# ACSN_v2.net
KiCad netlist of a schematic drawn in EAGLE
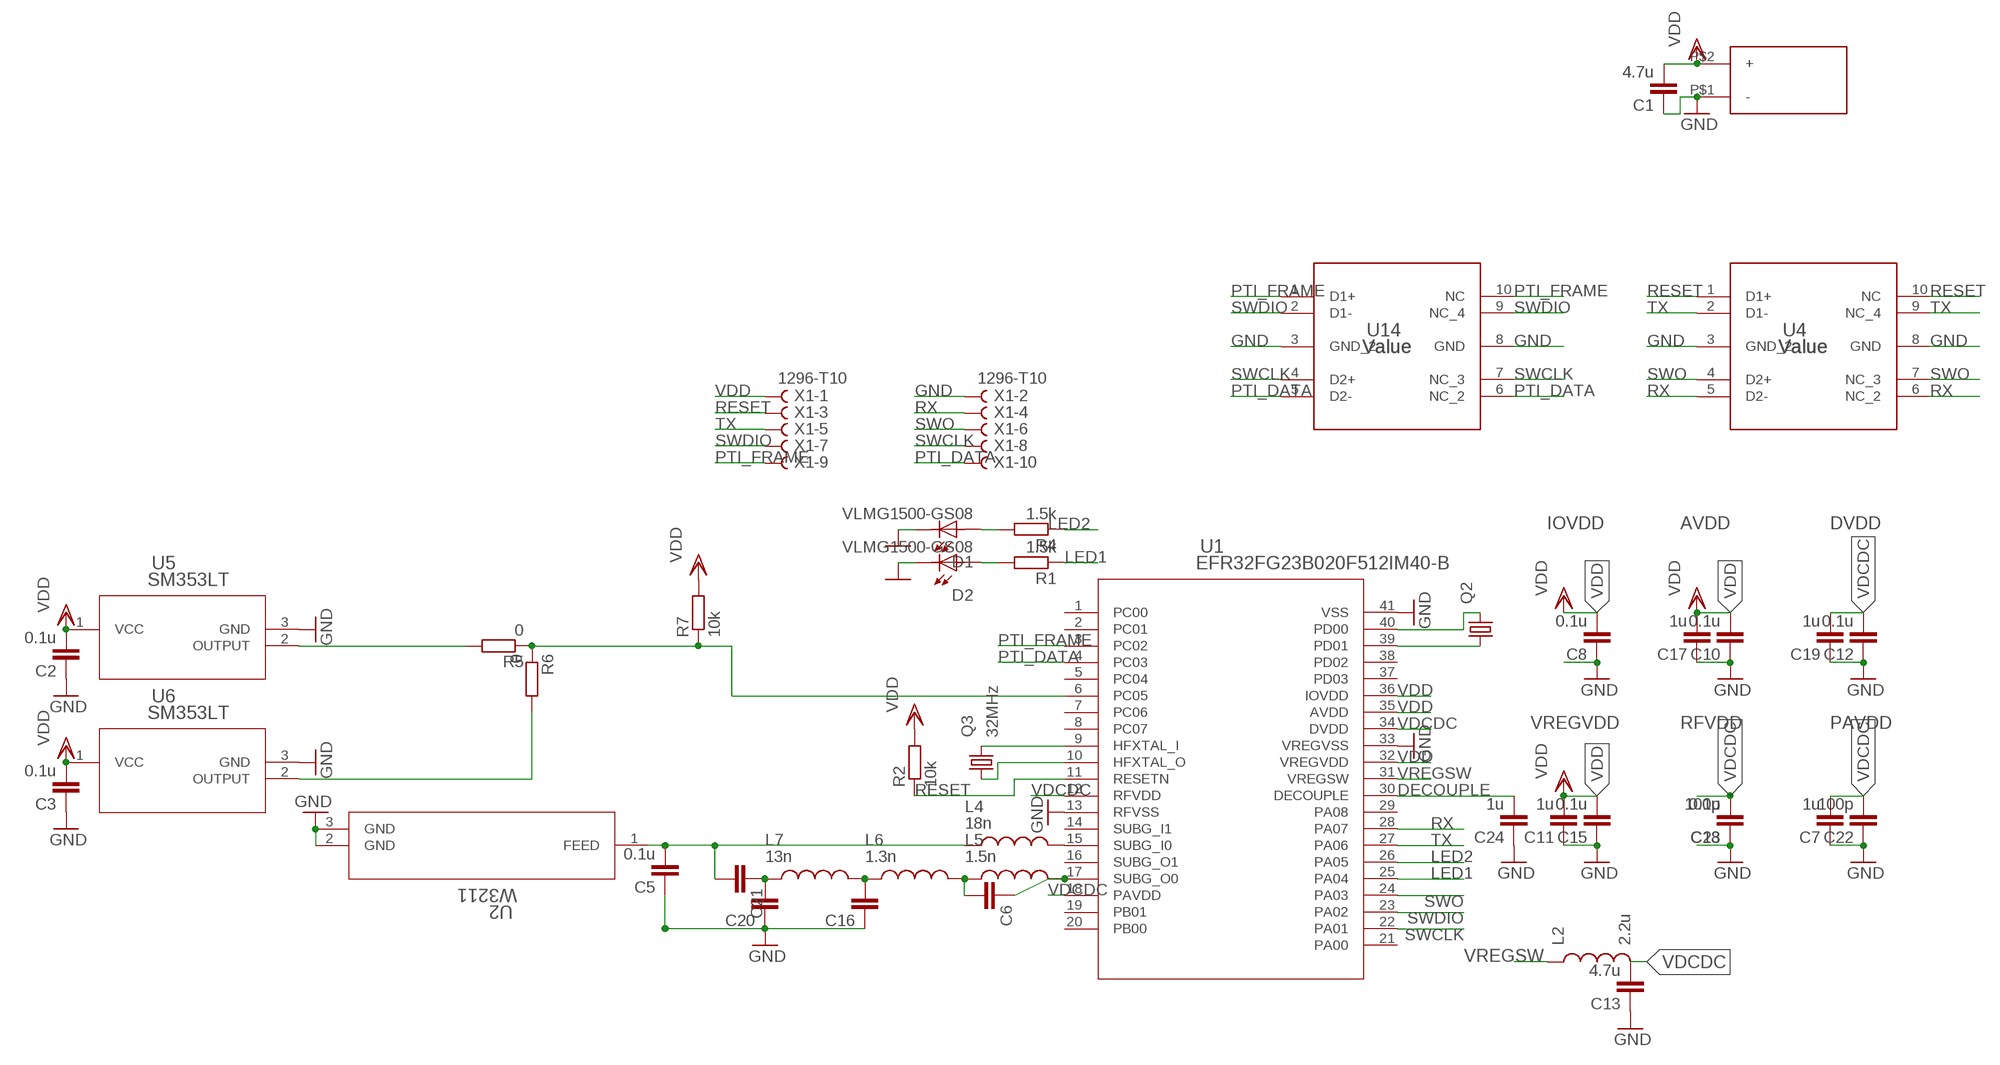
[diagram p0: schematic, sheet 1]

(export (version "E")
  (design (tool "Eeschema 10.0.6"))
  (components
    (comp (ref "C1")
      (value "4.7u")
      (footprint "eagle-import:C0603R")
      (libsource (lib "eagle-import") (part "CC0603R"))
    )
    (comp (ref "C2")
      (value "0.1u")
      (footprint "eagle-import:C0402")
      (libsource (lib "eagle-import") (part "CC0402"))
    )
    (comp (ref "C3")
      (value "0.1u")
      (footprint "eagle-import:C0402")
      (libsource (lib "eagle-import") (part "CC0402"))
    )
    (comp (ref "C5")
      (value "0.1u")
      (footprint "eagle-import:C0402")
      (libsource (lib "eagle-import") (part "CC0402"))
    )
    (comp (ref "C6")
      (value "1.9p")
      (footprint "eagle-import:C0402")
      (libsource (lib "eagle-import") (part "CC0402"))
    )
    (comp (ref "C7")
      (value "1u")
      (footprint "eagle-import:C0402")
      (libsource (lib "eagle-import") (part "CC0402"))
    )
    (comp (ref "C8")
      (value "0.1u")
      (footprint "eagle-import:C0402")
      (libsource (lib "eagle-import") (part "CC0402"))
    )
    (comp (ref "C10")
      (value "0.1u")
      (footprint "eagle-import:C0402")
      (libsource (lib "eagle-import") (part "CC0402"))
    )
    (comp (ref "C11")
      (value "1u")
      (footprint "eagle-import:C0402")
      (libsource (lib "eagle-import") (part "CC0402"))
    )
    (comp (ref "C12")
      (value "0.1u")
      (footprint "eagle-import:C0402")
      (libsource (lib "eagle-import") (part "CC0402"))
    )
    (comp (ref "C13")
      (value "4.7u")
      (footprint "eagle-import:C0603R")
      (libsource (lib "eagle-import") (part "CC0603R"))
    )
    (comp (ref "C15")
      (value "0.1u")
      (footprint "eagle-import:C0402")
      (libsource (lib "eagle-import") (part "CC0402"))
    )
    (comp (ref "C16")
      (value "7.2p")
      (footprint "eagle-import:C0402")
      (libsource (lib "eagle-import") (part "CC0402"))
    )
    (comp (ref "C17")
      (value "1u")
      (footprint "eagle-import:C0402")
      (libsource (lib "eagle-import") (part "CC0402"))
    )
    (comp (ref "C18")
      (value "0.1u")
      (footprint "eagle-import:C0402")
      (libsource (lib "eagle-import") (part "CC0402"))
    )
    (comp (ref "C19")
      (value "1u")
      (footprint "eagle-import:C0402")
      (libsource (lib "eagle-import") (part "CC0402"))
    )
    (comp (ref "C20")
      (value "1.3p")
      (footprint "eagle-import:C0402")
      (libsource (lib "eagle-import") (part "CC0402"))
    )
    (comp (ref "C21")
      (value "220p")
      (footprint "eagle-import:C0402")
      (libsource (lib "eagle-import") (part "CC0402"))
    )
    (comp (ref "C22")
      (value "100p")
      (footprint "eagle-import:C0402")
      (libsource (lib "eagle-import") (part "CC0402"))
    )
    (comp (ref "C23")
      (value "100p")
      (footprint "eagle-import:C0402")
      (libsource (lib "eagle-import") (part "CC0402"))
    )
    (comp (ref "C24")
      (value "1u")
      (footprint "eagle-import:C0402")
      (libsource (lib "eagle-import") (part "CC0402"))
    )
    (comp (ref "D1")
      (value "VLMG1500-GS08")
      (footprint "eagle-import:LEDC1005X35N")
      (fields (field (name "MF") "Vishay"))
      (libsource (lib "eagle-import") (part "VLMG1500-GS08"))
    )
    (comp (ref "D2")
      (value "VLMG1500-GS08")
      (footprint "eagle-import:LEDC1005X35N")
      (fields (field (name "MF") "Vishay"))
      (libsource (lib "eagle-import") (part "VLMG1500-GS08"))
    )
    (comp (ref "L2")
      (value "2.2u")
      (footprint "eagle-import:L0603")
      (libsource (lib "eagle-import") (part "INDUCTOR"))
    )
    (comp (ref "L4")
      (value "18n")
      (footprint "eagle-import:INDC0402X26N")
      (fields (field (name "MF") "TDK") (field (name "MP") "MHQ0402P7N5JT000"))
      (libsource (lib "eagle-import") (part "MHQ0402P7N5JT000"))
    )
    (comp (ref "L5")
      (value "1.5n")
      (footprint "eagle-import:INDC0402X26N")
      (fields (field (name "MF") "TDK") (field (name "MP") "MHQ0402P7N5JT000"))
      (libsource (lib "eagle-import") (part "MHQ0402P7N5JT000"))
    )
    (comp (ref "L6")
      (value "1.3n")
      (footprint "eagle-import:INDC0402X26N")
      (fields (field (name "MF") "TDK") (field (name "MP") "MHQ0402P7N5JT000"))
      (libsource (lib "eagle-import") (part "MHQ0402P7N5JT000"))
    )
    (comp (ref "L7")
      (value "13n")
      (footprint "eagle-import:INDC0402X26N")
      (fields (field (name "MF") "TDK") (field (name "MP") "MHQ0402P7N5JT000"))
      (libsource (lib "eagle-import") (part "MHQ0402P7N5JT000"))
    )
    (comp (ref "Q2")
      (value "KX-327-RT")
      (footprint "eagle-import:2.0X1.2")
      (libsource (lib "eagle-import") (part "KX-327-RT"))
    )
    (comp (ref "Q3")
      (value "32MHz")
      (footprint "eagle-import:2.0X1.6_KX-5")
      (libsource (lib "eagle-import") (part "KX-5"))
    )
    (comp (ref "R1")
      (value "1.5k")
      (footprint "eagle-import:R0402")
      (libsource (lib "eagle-import") (part "RR0402"))
    )
    (comp (ref "R2")
      (value "10k")
      (footprint "eagle-import:R0402")
      (libsource (lib "eagle-import") (part "RR0402"))
    )
    (comp (ref "R4")
      (value "1.5k")
      (footprint "eagle-import:R0402")
      (libsource (lib "eagle-import") (part "RR0402"))
    )
    (comp (ref "R5")
      (value "0")
      (footprint "eagle-import:R0402")
      (libsource (lib "eagle-import") (part "RR0402"))
    )
    (comp (ref "R6")
      (value "0")
      (footprint "eagle-import:R0402")
      (libsource (lib "eagle-import") (part "RR0402"))
    )
    (comp (ref "R7")
      (value "10k")
      (footprint "eagle-import:R0402")
      (libsource (lib "eagle-import") (part "RR0402"))
    )
    (comp (ref "U$2")
      (value "BS-24R")
      (footprint "eagle-import:BS-24")
      (libsource (lib "eagle-import") (part "BS-24R"))
    )
    (comp (ref "U1")
      (value "EFR32FG23B020F512IM40-B")
      (footprint "eagle-import:QFN_40_SIL")
      (fields (field (name "COPYRIGHT") "Copyright (C) 2022 Ultra Librarian. All rights reserved."))
      (libsource (lib "eagle-import") (part "EFR32FG23B020F512IM40-B"))
    )
    (comp (ref "U2")
      (value "W3211")
      (footprint "eagle-import:CHIP_3211_PUL")
      (fields (field (name "COPYRIGHT") "Copyright (C) 2022 Ultra Librarian. All rights reserved."))
      (libsource (lib "eagle-import") (part "W3211"))
    )
    (comp (ref "U4")
      (value "Value")
      (footprint "eagle-import:DQA0010A")
      (fields (field (name "MANUFACTURER") "Texas Instruments") (field (name "PARTNUMBER") "ESD204DQAR"))
      (libsource (lib "eagle-import") (part "ESD204DQAR"))
    )
    (comp (ref "U5")
      (value "SM353LT")
      (footprint "eagle-import:SM353LT_HNW")
      (fields (field (name "COPYRIGHT") "Copyright (C) 2022 Ultra Librarian. All rights reserved."))
      (libsource (lib "eagle-import") (part "SM353LT"))
    )
    (comp (ref "U6")
      (value "SM353LT")
      (footprint "eagle-import:SM353LT_HNW")
      (fields (field (name "COPYRIGHT") "Copyright (C) 2022 Ultra Librarian. All rights reserved."))
      (libsource (lib "eagle-import") (part "SM353LT"))
    )
    (comp (ref "U14")
      (value "Value")
      (footprint "eagle-import:DQA0010A")
      (fields (field (name "MANUFACTURER") "Texas Instruments") (field (name "PARTNUMBER") "ESD204DQAR"))
      (libsource (lib "eagle-import") (part "ESD204DQAR"))
    )
    (comp (ref "X1")
      (value "1296-T10")
      (footprint "eagle-import:1296-10")
      (libsource (lib "eagle-import") (part "1296-T10"))
    )
  )
  (nets
    (net (code "1") (name "/DECOUPLE") (class "Default")
      (node (ref "C24") (pin "2") (pinfunction "2_2") (pintype "passive"))
      (node (ref "U1") (pin "30") (pinfunction "DECOUPLE_30") (pintype "passive"))
    )
    (net (code "2") (name "/LED1") (class "Default")
      (node (ref "R1") (pin "1") (pinfunction "1_1") (pintype "passive"))
      (node (ref "U1") (pin "25") (pinfunction "PA04_25") (pintype "bidirectional"))
    )
    (net (code "3") (name "/LED2") (class "Default")
      (node (ref "R4") (pin "1") (pinfunction "1_1") (pintype "passive"))
      (node (ref "U1") (pin "26") (pinfunction "PA05_26") (pintype "bidirectional"))
    )
    (net (code "4") (name "/PTI_DATA") (class "Default")
      (node (ref "U1") (pin "4") (pinfunction "PC03_4") (pintype "bidirectional"))
      (node (ref "U14") (pin "5") (pinfunction "D2-_5") (pintype "bidirectional"))
      (node (ref "U14") (pin "6") (pinfunction "NC_2_6") (pintype "passive"))
      (node (ref "X1") (pin "10") (pinfunction "B_10") (pintype "passive"))
    )
    (net (code "5") (name "/PTI_FRAME") (class "Default")
      (node (ref "U1") (pin "3") (pinfunction "PC02_3") (pintype "bidirectional"))
      (node (ref "U14") (pin "1") (pinfunction "D1+_1") (pintype "bidirectional"))
      (node (ref "U14") (pin "10") (pinfunction "NC_10") (pintype "passive"))
      (node (ref "X1") (pin "9") (pinfunction "B_9") (pintype "passive"))
    )
    (net (code "6") (name "/RESET") (class "Default")
      (node (ref "R2") (pin "1") (pinfunction "1_1") (pintype "passive"))
      (node (ref "U1") (pin "11") (pinfunction "RESETN_11") (pintype "input"))
      (node (ref "U4") (pin "1") (pinfunction "D1+_1") (pintype "bidirectional"))
      (node (ref "U4") (pin "10") (pinfunction "NC_10") (pintype "passive"))
      (node (ref "X1") (pin "3") (pinfunction "B_3") (pintype "passive"))
    )
    (net (code "7") (name "/RX") (class "Default")
      (node (ref "U1") (pin "28") (pinfunction "PA07_28") (pintype "bidirectional"))
      (node (ref "U4") (pin "5") (pinfunction "D2-_5") (pintype "bidirectional"))
      (node (ref "U4") (pin "6") (pinfunction "NC_2_6") (pintype "passive"))
      (node (ref "X1") (pin "4") (pinfunction "B_4") (pintype "passive"))
    )
    (net (code "8") (name "/SWCLK") (class "Default")
      (node (ref "U1") (pin "22") (pinfunction "PA01_22") (pintype "bidirectional"))
      (node (ref "U14") (pin "4") (pinfunction "D2+_4") (pintype "bidirectional"))
      (node (ref "U14") (pin "7") (pinfunction "NC_3_7") (pintype "passive"))
      (node (ref "X1") (pin "8") (pinfunction "B_8") (pintype "passive"))
    )
    (net (code "9") (name "/SWDIO") (class "Default")
      (node (ref "U1") (pin "23") (pinfunction "PA02_23") (pintype "bidirectional"))
      (node (ref "U14") (pin "2") (pinfunction "D1-_2") (pintype "bidirectional"))
      (node (ref "U14") (pin "9") (pinfunction "NC_4_9") (pintype "passive"))
      (node (ref "X1") (pin "7") (pinfunction "B_7") (pintype "passive"))
    )
    (net (code "10") (name "/SWO") (class "Default")
      (node (ref "U1") (pin "24") (pinfunction "PA03_24") (pintype "bidirectional"))
      (node (ref "U4") (pin "4") (pinfunction "D2+_4") (pintype "bidirectional"))
      (node (ref "U4") (pin "7") (pinfunction "NC_3_7") (pintype "passive"))
      (node (ref "X1") (pin "6") (pinfunction "B_6") (pintype "passive"))
    )
    (net (code "11") (name "/TX") (class "Default")
      (node (ref "U1") (pin "27") (pinfunction "PA06_27") (pintype "bidirectional"))
      (node (ref "U4") (pin "2") (pinfunction "D1-_2") (pintype "bidirectional"))
      (node (ref "U4") (pin "9") (pinfunction "NC_4_9") (pintype "passive"))
      (node (ref "X1") (pin "5") (pinfunction "B_5") (pintype "passive"))
    )
    (net (code "12") (name "/VREGSW") (class "Default")
      (node (ref "L2") (pin "1") (pinfunction "1_1") (pintype "passive"))
      (node (ref "U1") (pin "31") (pinfunction "VREGSW_31") (pintype "power_in"))
    )
    (net (code "13") (name "GND") (class "Default")
      (node (ref "C1") (pin "1") (pinfunction "1_1") (pintype "passive"))
      (node (ref "C10") (pin "1") (pinfunction "1_1") (pintype "passive"))
      (node (ref "C11") (pin "1") (pinfunction "1_1") (pintype "passive"))
      (node (ref "C12") (pin "1") (pinfunction "1_1") (pintype "passive"))
      (node (ref "C13") (pin "1") (pinfunction "1_1") (pintype "passive"))
      (node (ref "C15") (pin "1") (pinfunction "1_1") (pintype "passive"))
      (node (ref "C16") (pin "1") (pinfunction "1_1") (pintype "passive"))
      (node (ref "C17") (pin "1") (pinfunction "1_1") (pintype "passive"))
      (node (ref "C18") (pin "1") (pinfunction "1_1") (pintype "passive"))
      (node (ref "C19") (pin "1") (pinfunction "1_1") (pintype "passive"))
      (node (ref "C2") (pin "1") (pinfunction "1_1") (pintype "passive"))
      (node (ref "C20") (pin "1") (pinfunction "1_1") (pintype "passive"))
      (node (ref "C22") (pin "1") (pinfunction "1_1") (pintype "passive"))
      (node (ref "C23") (pin "1") (pinfunction "1_1") (pintype "passive"))
      (node (ref "C24") (pin "1") (pinfunction "1_1") (pintype "passive"))
      (node (ref "C3") (pin "1") (pinfunction "1_1") (pintype "passive"))
      (node (ref "C5") (pin "1") (pinfunction "1_1") (pintype "passive"))
      (node (ref "C7") (pin "1") (pinfunction "1_1") (pintype "passive"))
      (node (ref "C8") (pin "1") (pinfunction "1_1") (pintype "passive"))
      (node (ref "D1") (pin "2") (pinfunction "2_2") (pintype "passive"))
      (node (ref "D2") (pin "2") (pinfunction "2_2") (pintype "passive"))
      (node (ref "U$2") (pin "P$1") (pinfunction "-_P$1") (pintype "bidirectional"))
      (node (ref "U1") (pin "13") (pinfunction "RFVSS_13") (pintype "power_in"))
      (node (ref "U1") (pin "33") (pinfunction "VREGVSS_33") (pintype "power_in"))
      (node (ref "U1") (pin "41") (pinfunction "VSS_41") (pintype "power_in"))
      (node (ref "U14") (pin "3") (pinfunction "GND_2_3") (pintype "power_in"))
      (node (ref "U14") (pin "8") (pinfunction "GND_8") (pintype "power_in"))
      (node (ref "U2") (pin "2") (pinfunction "GND_2") (pintype "passive"))
      (node (ref "U2") (pin "3") (pinfunction "GND_3") (pintype "passive"))
      (node (ref "U4") (pin "3") (pinfunction "GND_2_3") (pintype "power_in"))
      (node (ref "U4") (pin "8") (pinfunction "GND_8") (pintype "power_in"))
      (node (ref "U5") (pin "3") (pinfunction "GND_3") (pintype "passive"))
      (node (ref "U6") (pin "3") (pinfunction "GND_3") (pintype "passive"))
      (node (ref "X1") (pin "2") (pinfunction "B_2") (pintype "passive"))
    )
    (net (code "14") (name "Net-(C6-Pad2)") (class "Default")
      (node (ref "C6") (pin "2") (pinfunction "2_2") (pintype "passive"))
      (node (ref "L5") (pin "1") (pinfunction "1_1") (pintype "passive"))
      (node (ref "L6") (pin "2") (pinfunction "2_2") (pintype "passive"))
    )
    (net (code "15") (name "Net-(C16-Pad2)") (class "Default")
      (node (ref "C16") (pin "2") (pinfunction "2_2") (pintype "passive"))
      (node (ref "L6") (pin "1") (pinfunction "1_1") (pintype "passive"))
      (node (ref "L7") (pin "2") (pinfunction "2_2") (pintype "passive"))
    )
    (net (code "16") (name "Net-(C20-Pad2)") (class "Default")
      (node (ref "C20") (pin "2") (pinfunction "2_2") (pintype "passive"))
      (node (ref "C21") (pin "1") (pinfunction "1_1") (pintype "passive"))
      (node (ref "L7") (pin "1") (pinfunction "1_1") (pintype "passive"))
    )
    (net (code "17") (name "Net-(D1-Pad1)") (class "Default")
      (node (ref "D1") (pin "1") (pinfunction "1_1") (pintype "passive"))
      (node (ref "R4") (pin "2") (pinfunction "2_2") (pintype "passive"))
    )
    (net (code "18") (name "Net-(D2-Pad1)") (class "Default")
      (node (ref "D2") (pin "1") (pinfunction "1_1") (pintype "passive"))
      (node (ref "R1") (pin "2") (pinfunction "2_2") (pintype "passive"))
    )
    (net (code "19") (name "Net-(Q3-2)") (class "Default")
      (node (ref "Q3") (pin "3") (pinfunction "2_3") (pintype "passive"))
      (node (ref "U1") (pin "9") (pinfunction "HFXTAL_I_9") (pintype "input"))
    )
    (net (code "20") (name "Net-(U1-HFXTAL_O)") (class "Default")
      (node (ref "Q3") (pin "1") (pinfunction "1_1") (pintype "passive"))
      (node (ref "U1") (pin "10") (pinfunction "HFXTAL_O_10") (pintype "output"))
    )
    (net (code "21") (name "Net-(U1-PC05)") (class "Default")
      (node (ref "R5") (pin "1") (pinfunction "1_1") (pintype "passive"))
      (node (ref "R6") (pin "1") (pinfunction "1_1") (pintype "passive"))
      (node (ref "R7") (pin "1") (pinfunction "1_1") (pintype "passive"))
      (node (ref "U1") (pin "6") (pinfunction "PC05_6") (pintype "bidirectional"))
    )
    (net (code "22") (name "Net-(U1-PD00)") (class "Default")
      (node (ref "Q2") (pin "2") (pinfunction "2_2") (pintype "passive"))
      (node (ref "U1") (pin "40") (pinfunction "PD00_40") (pintype "bidirectional"))
    )
    (net (code "23") (name "Net-(U1-PD01)") (class "Default")
      (node (ref "Q2") (pin "1") (pinfunction "1_1") (pintype "passive"))
      (node (ref "U1") (pin "39") (pinfunction "PD01_39") (pintype "bidirectional"))
    )
    (net (code "24") (name "Net-(U1-SUBG_I0)") (class "Default")
      (node (ref "L4") (pin "2") (pinfunction "2_2") (pintype "passive"))
      (node (ref "U1") (pin "15") (pinfunction "SUBG_I0_15") (pintype "input"))
    )
    (net (code "25") (name "Net-(U1-SUBG_O0)") (class "Default")
      (node (ref "C6") (pin "1") (pinfunction "1_1") (pintype "passive"))
      (node (ref "L5") (pin "2") (pinfunction "2_2") (pintype "passive"))
      (node (ref "U1") (pin "17") (pinfunction "SUBG_O0_17") (pintype "output"))
    )
    (net (code "26") (name "Net-(U2-FEED)") (class "Default")
      (node (ref "C21") (pin "2") (pinfunction "2_2") (pintype "passive"))
      (node (ref "C5") (pin "2") (pinfunction "2_2") (pintype "passive"))
      (node (ref "L4") (pin "1") (pinfunction "1_1") (pintype "passive"))
      (node (ref "U2") (pin "1") (pinfunction "FEED_1") (pintype "passive"))
    )
    (net (code "27") (name "Net-(U5-OUTPUT)") (class "Default")
      (node (ref "R5") (pin "2") (pinfunction "2_2") (pintype "passive"))
      (node (ref "U5") (pin "2") (pinfunction "OUTPUT_2") (pintype "output"))
    )
    (net (code "28") (name "Net-(U6-OUTPUT)") (class "Default")
      (node (ref "R6") (pin "2") (pinfunction "2_2") (pintype "passive"))
      (node (ref "U6") (pin "2") (pinfunction "OUTPUT_2") (pintype "output"))
    )
    (net (code "29") (name "VDCDC") (class "Default")
      (node (ref "C12") (pin "2") (pinfunction "2_2") (pintype "passive"))
      (node (ref "C13") (pin "2") (pinfunction "2_2") (pintype "passive"))
      (node (ref "C18") (pin "2") (pinfunction "2_2") (pintype "passive"))
      (node (ref "C19") (pin "2") (pinfunction "2_2") (pintype "passive"))
      (node (ref "C22") (pin "2") (pinfunction "2_2") (pintype "passive"))
      (node (ref "C23") (pin "2") (pinfunction "2_2") (pintype "passive"))
      (node (ref "C7") (pin "2") (pinfunction "2_2") (pintype "passive"))
      (node (ref "L2") (pin "2") (pinfunction "2_2") (pintype "passive"))
      (node (ref "U1") (pin "12") (pinfunction "RFVDD_12") (pintype "power_in"))
      (node (ref "U1") (pin "18") (pinfunction "PAVDD_18") (pintype "power_in"))
      (node (ref "U1") (pin "34") (pinfunction "DVDD_34") (pintype "power_in"))
    )
    (net (code "30") (name "VDD") (class "Default")
      (node (ref "C1") (pin "2") (pinfunction "2_2") (pintype "passive"))
      (node (ref "C10") (pin "2") (pinfunction "2_2") (pintype "passive"))
      (node (ref "C11") (pin "2") (pinfunction "2_2") (pintype "passive"))
      (node (ref "C15") (pin "2") (pinfunction "2_2") (pintype "passive"))
      (node (ref "C17") (pin "2") (pinfunction "2_2") (pintype "passive"))
      (node (ref "C2") (pin "2") (pinfunction "2_2") (pintype "passive"))
      (node (ref "C3") (pin "2") (pinfunction "2_2") (pintype "passive"))
      (node (ref "C8") (pin "2") (pinfunction "2_2") (pintype "passive"))
      (node (ref "R2") (pin "2") (pinfunction "2_2") (pintype "passive"))
      (node (ref "R7") (pin "2") (pinfunction "2_2") (pintype "passive"))
      (node (ref "U$2") (pin "P$2") (pinfunction "+_P$2") (pintype "bidirectional"))
      (node (ref "U1") (pin "32") (pinfunction "VREGVDD_32") (pintype "power_in"))
      (node (ref "U1") (pin "35") (pinfunction "AVDD_35") (pintype "power_in"))
      (node (ref "U1") (pin "36") (pinfunction "IOVDD_36") (pintype "power_in"))
      (node (ref "U5") (pin "1") (pinfunction "VCC_1") (pintype "power_in"))
      (node (ref "U6") (pin "1") (pinfunction "VCC_1") (pintype "power_in"))
      (node (ref "X1") (pin "1") (pinfunction "B_1") (pintype "passive"))
    )
    (net (code "31") (name "unconnected-(U1-PA00-Pad21)") (class "Default")
      (node (ref "U1") (pin "21") (pinfunction "PA00_21") (pintype "bidirectional"))
    )
    (net (code "32") (name "unconnected-(U1-PA08-Pad29)") (class "Default")
      (node (ref "U1") (pin "29") (pinfunction "PA08_29") (pintype "bidirectional"))
    )
    (net (code "33") (name "unconnected-(U1-PB00-Pad20)") (class "Default")
      (node (ref "U1") (pin "20") (pinfunction "PB00_20") (pintype "bidirectional"))
    )
    (net (code "34") (name "unconnected-(U1-PB01-Pad19)") (class "Default")
      (node (ref "U1") (pin "19") (pinfunction "PB01_19") (pintype "bidirectional"))
    )
    (net (code "35") (name "unconnected-(U1-PC00-Pad1)") (class "Default")
      (node (ref "U1") (pin "1") (pinfunction "PC00_1") (pintype "bidirectional"))
    )
    (net (code "36") (name "unconnected-(U1-PC01-Pad2)") (class "Default")
      (node (ref "U1") (pin "2") (pinfunction "PC01_2") (pintype "bidirectional"))
    )
    (net (code "37") (name "unconnected-(U1-PC04-Pad5)") (class "Default")
      (node (ref "U1") (pin "5") (pinfunction "PC04_5") (pintype "bidirectional"))
    )
    (net (code "38") (name "unconnected-(U1-PC06-Pad7)") (class "Default")
      (node (ref "U1") (pin "7") (pinfunction "PC06_7") (pintype "bidirectional"))
    )
    (net (code "39") (name "unconnected-(U1-PC07-Pad8)") (class "Default")
      (node (ref "U1") (pin "8") (pinfunction "PC07_8") (pintype "bidirectional"))
    )
    (net (code "40") (name "unconnected-(U1-PD02-Pad38)") (class "Default")
      (node (ref "U1") (pin "38") (pinfunction "PD02_38") (pintype "bidirectional"))
    )
    (net (code "41") (name "unconnected-(U1-PD03-Pad37)") (class "Default")
      (node (ref "U1") (pin "37") (pinfunction "PD03_37") (pintype "bidirectional"))
    )
    (net (code "42") (name "unconnected-(U1-SUBG_I1-Pad14)") (class "Default")
      (node (ref "U1") (pin "14") (pinfunction "SUBG_I1_14") (pintype "input"))
    )
    (net (code "43") (name "unconnected-(U1-SUBG_O1-Pad16)") (class "Default")
      (node (ref "U1") (pin "16") (pinfunction "SUBG_O1_16") (pintype "output"))
    )
  )
)
